# Connectors_and_Regs.net
KiCad netlist of a schematic drawn in Altium Designer
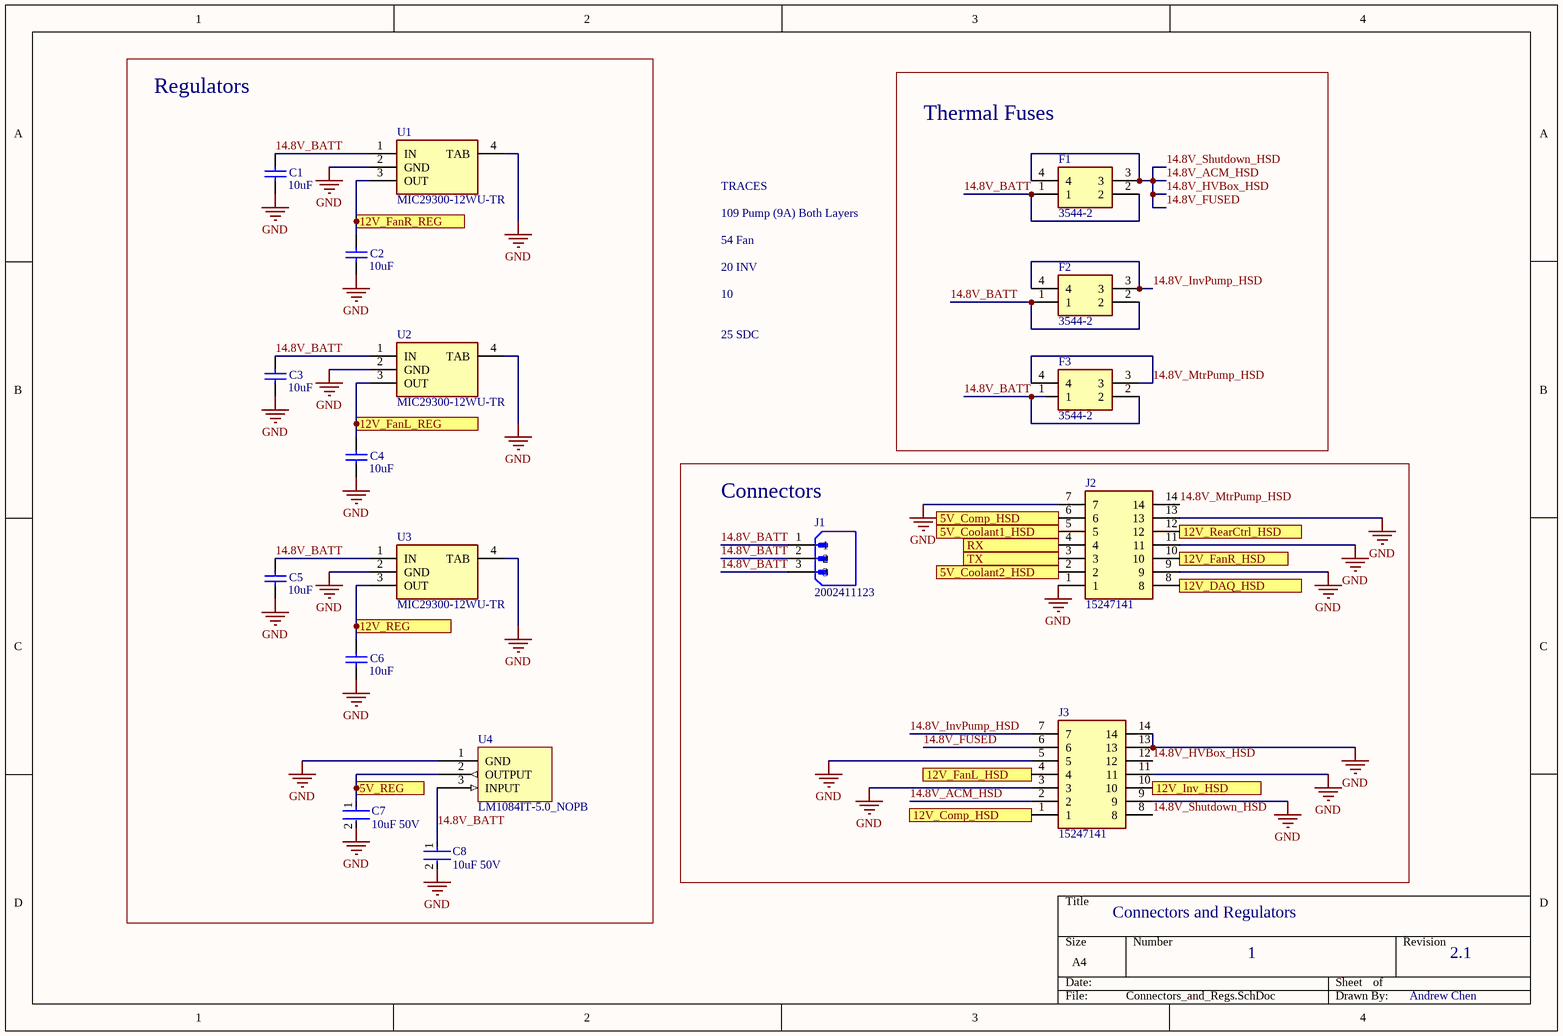
[diagram p0: Connectors_and_Regs.SchDoc]

(export (version "E")
  (design (tool "Eeschema 10.0.6"))
  (components
    (comp (ref "C1")
      (value "10uF")
      (footprint "C1206")
      (description "Capacitor (Semiconductor SIM Model)")
      (fields (field (name "PUBLISHER") "Altium Limited"))
      (libsource (lib "Miscellaneous Devices") (part "Cap Semi"))
    )
    (comp (ref "C2")
      (value "10uF")
      (footprint "C1206")
      (description "Capacitor (Semiconductor SIM Model)")
      (fields (field (name "PUBLISHER") "Altium Limited"))
      (libsource (lib "Miscellaneous Devices") (part "Cap Semi"))
    )
    (comp (ref "C3")
      (value "10uF")
      (footprint "C1206")
      (description "Capacitor (Semiconductor SIM Model)")
      (fields (field (name "PUBLISHER") "Altium Limited"))
      (libsource (lib "Miscellaneous Devices") (part "Cap Semi"))
    )
    (comp (ref "C4")
      (value "10uF")
      (footprint "C1206")
      (description "Capacitor (Semiconductor SIM Model)")
      (fields (field (name "PUBLISHER") "Altium Limited"))
      (libsource (lib "Miscellaneous Devices") (part "Cap Semi"))
    )
    (comp (ref "C5")
      (value "10uF")
      (footprint "C1206")
      (description "Capacitor (Semiconductor SIM Model)")
      (fields (field (name "PUBLISHER") "Altium Limited"))
      (libsource (lib "Miscellaneous Devices") (part "Cap Semi"))
    )
    (comp (ref "C6")
      (value "10uF")
      (footprint "C1206")
      (description "Capacitor (Semiconductor SIM Model)")
      (fields (field (name "PUBLISHER") "Altium Limited"))
      (libsource (lib "Miscellaneous Devices") (part "Cap Semi"))
    )
    (comp (ref "C7")
      (value "10uF 50V")
      (footprint "FP-CL31-IPC_A")
      (description "Cap Ceramic 4.7uF 16V X7R ±10% SMD 1206 +125°C Embossed T/R")
      (fields (field (name "TOLERANCE") "10%"))
      (libsource (lib "Altium Content Vault") (part "b4654b650e69147ec39a6b967a45e02"))
    )
    (comp (ref "C8")
      (value "10uF 50V")
      (footprint "FP-CL31-IPC_A")
      (description "Cap Ceramic 4.7uF 16V X7R ±10% SMD 1206 +125°C Embossed T/R")
      (fields (field (name "TOLERANCE") "10%"))
      (libsource (lib "Altium Content Vault") (part "b4654b650e69147ec39a6b967a45e02"))
    )
    (comp (ref "F1")
      (value "3544-2")
      (footprint "3544-2")
      (description "Fuse")
      (fields
        (field (name "MANUFACTURER_PART_NUMBER") "3549-2")
        (field (name "MOUSER PART NUMBER") "534-3549-2")
      )
      (libsource (lib "*") (part "3549-2"))
    )
    (comp (ref "F2")
      (value "3544-2")
      (footprint "3544-2")
      (description "Fuse")
      (fields
        (field (name "MANUFACTURER_PART_NUMBER") "3549-2")
        (field (name "MOUSER PART NUMBER") "534-3549-2")
      )
      (libsource (lib "*") (part "3549-2"))
    )
    (comp (ref "F3")
      (value "3544-2")
      (footprint "3544-2")
      (description "Fuse")
      (fields
        (field (name "MANUFACTURER_PART_NUMBER") "3549-2")
        (field (name "MOUSER PART NUMBER") "534-3549-2")
      )
      (libsource (lib "*") (part "3549-2"))
    )
    (comp (ref "J1")
      (value "2002411123")
      (footprint "2002411YY3_11/12/13")
      (libsource (lib "2002411123") (part "2002411123"))
    )
    (comp (ref "J2")
      (value "15247141")
      (footprint "MOLEX_15247141")
      (description "Connector")
      (fields (field (name "MANUFACTURER_PART_NUMBER") "15246142"))
      (libsource (lib "*") (part "15246142"))
    )
    (comp (ref "J3")
      (value "15247141")
      (footprint "MOLEX_15247141")
      (description "Connector")
      (fields (field (name "MANUFACTURER_PART_NUMBER") "15246142"))
      (libsource (lib "*") (part "15246142"))
    )
    (comp (ref "U1")
      (value "MIC29300-12WU-TR")
      (footprint "MIC2930012WUTR")
      (description "Integrated Circuit")
      (fields (field (name "MOUSER PART NUMBER") "998-MIC29300-12WUTR"))
      (libsource (lib "MIC29300-12WU") (part "MIC29300-12WU-TR"))
    )
    (comp (ref "U2")
      (value "MIC29300-12WU-TR")
      (footprint "MIC2930012WUTR")
      (description "Integrated Circuit")
      (fields (field (name "MOUSER PART NUMBER") "998-MIC29300-12WUTR"))
      (libsource (lib "MIC29300-12WU") (part "MIC29300-12WU-TR"))
    )
    (comp (ref "U3")
      (value "MIC29300-12WU-TR")
      (footprint "MIC2930012WUTR")
      (description "Integrated Circuit")
      (fields (field (name "MOUSER PART NUMBER") "998-MIC29300-12WUTR"))
      (libsource (lib "MIC29300-12WU") (part "MIC29300-12WU-TR"))
    )
    (comp (ref "U4")
      (value "LM1084IT-5.0_NOPB")
      (footprint "TO254P470X1028X1955-3P")
      (libsource (lib "Schlib1") (part "LM1084IT-5.0_NOPB"))
    )
  )
  (nets
    (net (code "1") (name "/5V_Comp_HSD") (class "Default")
      (node (ref "J2") (pin "6") (pinfunction "6_6") (pintype "passive"))
    )
    (net (code "2") (name "/5V_Coolant1_HSD") (class "Default")
      (node (ref "J2") (pin "5") (pinfunction "5_5") (pintype "passive"))
    )
    (net (code "3") (name "/5V_Coolant2_HSD") (class "Default")
      (node (ref "J2") (pin "2") (pinfunction "2_2") (pintype "passive"))
    )
    (net (code "4") (name "/5V_REG") (class "Default")
      (node (ref "C7") (pin "1") (pinfunction "1_1") (pintype "passive"))
      (node (ref "U4") (pin "2") (pintype "output"))
    )
    (net (code "5") (name "/12V_Comp_HSD") (class "Default")
      (node (ref "J3") (pin "1") (pinfunction "1_1") (pintype "passive"))
    )
    (net (code "6") (name "/12V_DAQ_HSD") (class "Default")
      (node (ref "J2") (pin "8") (pinfunction "8_8") (pintype "passive"))
    )
    (net (code "7") (name "/12V_FanL_HSD") (class "Default")
      (node (ref "J3") (pin "4") (pinfunction "4_4") (pintype "passive"))
    )
    (net (code "8") (name "/12V_FanL_REG") (class "Default")
      (node (ref "C4") (pin "1") (pinfunction "1_1") (pintype "passive"))
      (node (ref "U2") (pin "3") (pinfunction "OUT_3") (pintype "passive"))
    )
    (net (code "9") (name "/12V_FanR_HSD") (class "Default")
      (node (ref "J2") (pin "10") (pinfunction "10_10") (pintype "passive"))
    )
    (net (code "10") (name "/12V_FanR_REG") (class "Default")
      (node (ref "C2") (pin "1") (pinfunction "1_1") (pintype "passive"))
      (node (ref "U1") (pin "3") (pinfunction "OUT_3") (pintype "passive"))
    )
    (net (code "11") (name "/12V_Inv_HSD") (class "Default")
      (node (ref "J3") (pin "10") (pinfunction "10_10") (pintype "passive"))
    )
    (net (code "12") (name "/12V_REG") (class "Default")
      (node (ref "C6") (pin "1") (pinfunction "1_1") (pintype "passive"))
      (node (ref "U3") (pin "3") (pinfunction "OUT_3") (pintype "passive"))
    )
    (net (code "13") (name "/12V_RearCtrl_HSD") (class "Default")
      (node (ref "J2") (pin "12") (pinfunction "12_12") (pintype "passive"))
    )
    (net (code "14") (name "/14.8V_ACM_HSD") (class "Default")
      (node (ref "F1") (pin "3") (pinfunction "3_3") (pintype "passive"))
      (node (ref "F1") (pin "4") (pinfunction "4_4") (pintype "passive"))
      (node (ref "J3") (pin "12") (pinfunction "12_12") (pintype "passive"))
      (node (ref "J3") (pin "2") (pinfunction "2_2") (pintype "passive"))
      (node (ref "J3") (pin "6") (pinfunction "6_6") (pintype "passive"))
      (node (ref "J3") (pin "8") (pinfunction "8_8") (pintype "passive"))
    )
    (net (code "15") (name "/14.8V_BATT") (class "Default")
      (node (ref "C1") (pin "1") (pinfunction "1_1") (pintype "passive"))
      (node (ref "C3") (pin "1") (pinfunction "1_1") (pintype "passive"))
      (node (ref "C5") (pin "1") (pinfunction "1_1") (pintype "passive"))
      (node (ref "C8") (pin "1") (pinfunction "1_1") (pintype "passive"))
      (node (ref "F1") (pin "1") (pinfunction "1_1") (pintype "passive"))
      (node (ref "F1") (pin "2") (pinfunction "2_2") (pintype "passive"))
      (node (ref "F2") (pin "1") (pinfunction "1_1") (pintype "passive"))
      (node (ref "F2") (pin "2") (pinfunction "2_2") (pintype "passive"))
      (node (ref "F3") (pin "1") (pinfunction "1_1") (pintype "passive"))
      (node (ref "F3") (pin "2") (pinfunction "2_2") (pintype "passive"))
      (node (ref "J1") (pin "1") (pinfunction "1_1") (pintype "passive"))
      (node (ref "J1") (pin "2") (pinfunction "2_2") (pintype "passive"))
      (node (ref "J1") (pin "3") (pinfunction "3_3") (pintype "passive"))
      (node (ref "U1") (pin "1") (pinfunction "IN_1") (pintype "passive"))
      (node (ref "U2") (pin "1") (pinfunction "IN_1") (pintype "passive"))
      (node (ref "U3") (pin "1") (pinfunction "IN_1") (pintype "passive"))
      (node (ref "U4") (pin "3") (pintype "input"))
    )
    (net (code "16") (name "/14.8V_InvPump_HSD") (class "Default")
      (node (ref "F2") (pin "3") (pinfunction "3_3") (pintype "passive"))
      (node (ref "F2") (pin "4") (pinfunction "4_4") (pintype "passive"))
      (node (ref "J3") (pin "7") (pinfunction "7_7") (pintype "passive"))
    )
    (net (code "17") (name "/14.8V_MtrPump_HSD") (class "Default")
      (node (ref "F3") (pin "3") (pinfunction "3_3") (pintype "passive"))
      (node (ref "F3") (pin "4") (pinfunction "4_4") (pintype "passive"))
      (node (ref "J2") (pin "14") (pinfunction "14_14") (pintype "passive"))
    )
    (net (code "18") (name "/RX") (class "Default")
      (node (ref "J2") (pin "4") (pinfunction "4_4") (pintype "passive"))
    )
    (net (code "19") (name "/TX") (class "Default")
      (node (ref "J2") (pin "3") (pinfunction "3_3") (pintype "passive"))
    )
    (net (code "20") (name "GND") (class "Default")
      (node (ref "C1") (pin "2") (pinfunction "2_2") (pintype "passive"))
      (node (ref "C2") (pin "2") (pinfunction "2_2") (pintype "passive"))
      (node (ref "C3") (pin "2") (pinfunction "2_2") (pintype "passive"))
      (node (ref "C4") (pin "2") (pinfunction "2_2") (pintype "passive"))
      (node (ref "C5") (pin "2") (pinfunction "2_2") (pintype "passive"))
      (node (ref "C6") (pin "2") (pinfunction "2_2") (pintype "passive"))
      (node (ref "C7") (pin "2") (pinfunction "2_2") (pintype "passive"))
      (node (ref "C8") (pin "2") (pinfunction "2_2") (pintype "passive"))
      (node (ref "J2") (pin "1") (pinfunction "1_1") (pintype "passive"))
      (node (ref "J2") (pin "11") (pinfunction "11_11") (pintype "passive"))
      (node (ref "J2") (pin "13") (pinfunction "13_13") (pintype "passive"))
      (node (ref "J2") (pin "7") (pinfunction "7_7") (pintype "passive"))
      (node (ref "J2") (pin "9") (pinfunction "9_9") (pintype "passive"))
      (node (ref "J3") (pin "11") (pinfunction "11_11") (pintype "passive"))
      (node (ref "J3") (pin "13") (pinfunction "13_13") (pintype "passive"))
      (node (ref "J3") (pin "14") (pinfunction "14_14") (pintype "passive"))
      (node (ref "J3") (pin "3") (pinfunction "3_3") (pintype "passive"))
      (node (ref "J3") (pin "5") (pinfunction "5_5") (pintype "passive"))
      (node (ref "J3") (pin "9") (pinfunction "9_9") (pintype "passive"))
      (node (ref "U1") (pin "2") (pinfunction "GND_2") (pintype "passive"))
      (node (ref "U1") (pin "4") (pinfunction "TAB_4") (pintype "passive"))
      (node (ref "U2") (pin "2") (pinfunction "GND_2") (pintype "passive"))
      (node (ref "U2") (pin "4") (pinfunction "TAB_4") (pintype "passive"))
      (node (ref "U3") (pin "2") (pinfunction "GND_2") (pintype "passive"))
      (node (ref "U3") (pin "4") (pinfunction "TAB_4") (pintype "passive"))
      (node (ref "U4") (pin "1") (pintype "power_in"))
    )
  )
)
